# SCH_02_Electrodes.net
KiCad netlist of a schematic drawn in Altium Designer
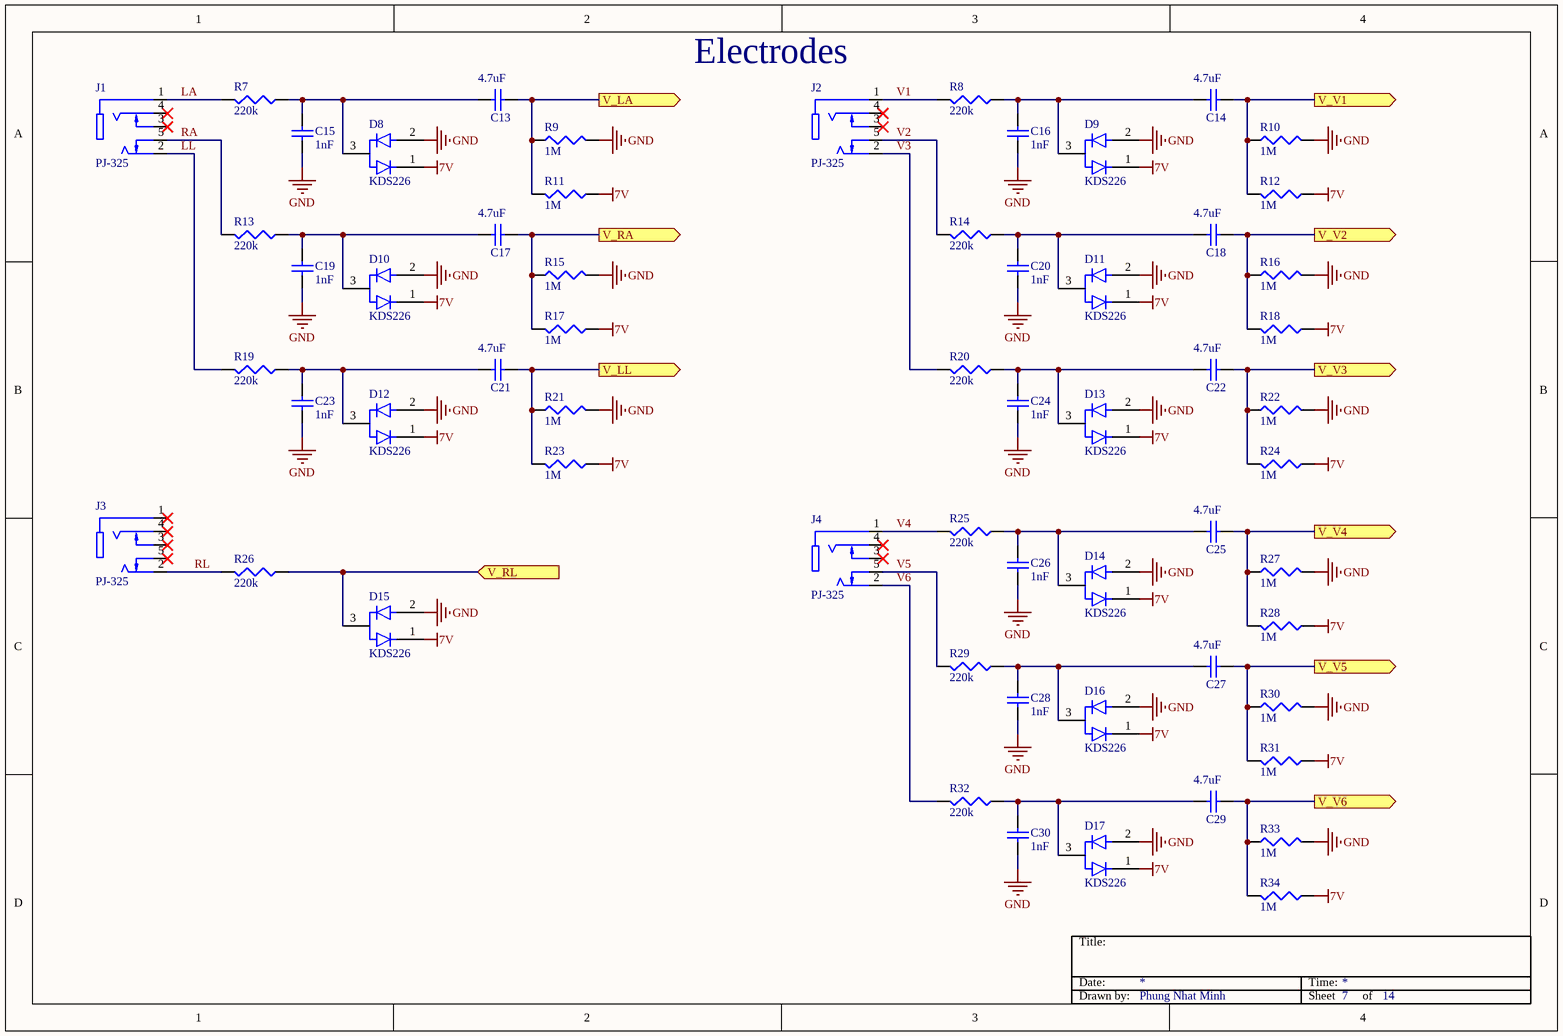
[diagram p0: SCH_02_Electrodes.SchDoc]

(export (version "E")
  (design (tool "Eeschema 10.0.6"))
  (components
    (comp (ref "C13")
      (value "4.7uF")
      (footprint "WCAP-CSGP_0603_L1.6W0.8H0.8_Reflow")
      (description "WCAP-CSGP Multilayer Ceramic Chip Capacitor, General Purpose, size 0603, X5R, 4.7uF, 10VDC")
      (fields
        (field (name "MANUFACTURER PART NUMBER") "885012106012")
        (field (name "MANUFACTURER") "Wurth Elektronik")
      )
      (libsource (lib "Altium_WCAP-CSGP (rev24b)") (part "885012106012"))
    )
    (comp (ref "C14")
      (value "4.7uF")
      (footprint "WCAP-CSGP_0603_L1.6W0.8H0.8_Reflow")
      (description "WCAP-CSGP Multilayer Ceramic Chip Capacitor, General Purpose, size 0603, X5R, 4.7uF, 10VDC")
      (fields
        (field (name "MANUFACTURER PART NUMBER") "885012106012")
        (field (name "MANUFACTURER") "Wurth Elektronik")
      )
      (libsource (lib "Altium_WCAP-CSGP (rev24b)") (part "885012106012"))
    )
    (comp (ref "C15")
      (value "1nF")
      (footprint "WCAP-CSGP_0603_L1.6W0.8H0.8_Reflow")
      (description "WCAP-CSGP Multilayer Ceramic Chip Capacitor, General Purpose, size 0603, NP0, 1nF, 50VDC")
      (fields
        (field (name "MANUFACTURER PART NUMBER") "885012006063")
        (field (name "MANUFACTURER") "Wurth Elektronik")
      )
      (libsource (lib "Altium_WCAP-CSGP (rev24b)") (part "885012006063"))
    )
    (comp (ref "C16")
      (value "1nF")
      (footprint "WCAP-CSGP_0603_L1.6W0.8H0.8_Reflow")
      (description "WCAP-CSGP Multilayer Ceramic Chip Capacitor, General Purpose, size 0603, NP0, 1nF, 50VDC")
      (fields
        (field (name "MANUFACTURER PART NUMBER") "885012006063")
        (field (name "MANUFACTURER") "Wurth Elektronik")
      )
      (libsource (lib "Altium_WCAP-CSGP (rev24b)") (part "885012006063"))
    )
    (comp (ref "C17")
      (value "4.7uF")
      (footprint "WCAP-CSGP_0603_L1.6W0.8H0.8_Reflow")
      (description "WCAP-CSGP Multilayer Ceramic Chip Capacitor, General Purpose, size 0603, X5R, 4.7uF, 10VDC")
      (fields
        (field (name "MANUFACTURER PART NUMBER") "885012106012")
        (field (name "MANUFACTURER") "Wurth Elektronik")
      )
      (libsource (lib "Altium_WCAP-CSGP (rev24b)") (part "885012106012"))
    )
    (comp (ref "C18")
      (value "4.7uF")
      (footprint "WCAP-CSGP_0603_L1.6W0.8H0.8_Reflow")
      (description "WCAP-CSGP Multilayer Ceramic Chip Capacitor, General Purpose, size 0603, X5R, 4.7uF, 10VDC")
      (fields
        (field (name "MANUFACTURER PART NUMBER") "885012106012")
        (field (name "MANUFACTURER") "Wurth Elektronik")
      )
      (libsource (lib "Altium_WCAP-CSGP (rev24b)") (part "885012106012"))
    )
    (comp (ref "C19")
      (value "1nF")
      (footprint "WCAP-CSGP_0603_L1.6W0.8H0.8_Reflow")
      (description "WCAP-CSGP Multilayer Ceramic Chip Capacitor, General Purpose, size 0603, NP0, 1nF, 50VDC")
      (fields
        (field (name "MANUFACTURER PART NUMBER") "885012006063")
        (field (name "MANUFACTURER") "Wurth Elektronik")
      )
      (libsource (lib "Altium_WCAP-CSGP (rev24b)") (part "885012006063"))
    )
    (comp (ref "C20")
      (value "1nF")
      (footprint "WCAP-CSGP_0603_L1.6W0.8H0.8_Reflow")
      (description "WCAP-CSGP Multilayer Ceramic Chip Capacitor, General Purpose, size 0603, NP0, 1nF, 50VDC")
      (fields
        (field (name "MANUFACTURER PART NUMBER") "885012006063")
        (field (name "MANUFACTURER") "Wurth Elektronik")
      )
      (libsource (lib "Altium_WCAP-CSGP (rev24b)") (part "885012006063"))
    )
    (comp (ref "C21")
      (value "4.7uF")
      (footprint "WCAP-CSGP_0603_L1.6W0.8H0.8_Reflow")
      (description "WCAP-CSGP Multilayer Ceramic Chip Capacitor, General Purpose, size 0603, X5R, 4.7uF, 10VDC")
      (fields
        (field (name "MANUFACTURER PART NUMBER") "885012106012")
        (field (name "MANUFACTURER") "Wurth Elektronik")
      )
      (libsource (lib "Altium_WCAP-CSGP (rev24b)") (part "885012106012"))
    )
    (comp (ref "C22")
      (value "4.7uF")
      (footprint "WCAP-CSGP_0603_L1.6W0.8H0.8_Reflow")
      (description "WCAP-CSGP Multilayer Ceramic Chip Capacitor, General Purpose, size 0603, X5R, 4.7uF, 10VDC")
      (fields
        (field (name "MANUFACTURER PART NUMBER") "885012106012")
        (field (name "MANUFACTURER") "Wurth Elektronik")
      )
      (libsource (lib "Altium_WCAP-CSGP (rev24b)") (part "885012106012"))
    )
    (comp (ref "C23")
      (value "1nF")
      (footprint "WCAP-CSGP_0603_L1.6W0.8H0.8_Reflow")
      (description "WCAP-CSGP Multilayer Ceramic Chip Capacitor, General Purpose, size 0603, NP0, 1nF, 50VDC")
      (fields
        (field (name "MANUFACTURER PART NUMBER") "885012006063")
        (field (name "MANUFACTURER") "Wurth Elektronik")
      )
      (libsource (lib "Altium_WCAP-CSGP (rev24b)") (part "885012006063"))
    )
    (comp (ref "C24")
      (value "1nF")
      (footprint "WCAP-CSGP_0603_L1.6W0.8H0.8_Reflow")
      (description "WCAP-CSGP Multilayer Ceramic Chip Capacitor, General Purpose, size 0603, NP0, 1nF, 50VDC")
      (fields
        (field (name "MANUFACTURER PART NUMBER") "885012006063")
        (field (name "MANUFACTURER") "Wurth Elektronik")
      )
      (libsource (lib "Altium_WCAP-CSGP (rev24b)") (part "885012006063"))
    )
    (comp (ref "C25")
      (value "4.7uF")
      (footprint "WCAP-CSGP_0603_L1.6W0.8H0.8_Reflow")
      (description "WCAP-CSGP Multilayer Ceramic Chip Capacitor, General Purpose, size 0603, X5R, 4.7uF, 10VDC")
      (fields
        (field (name "MANUFACTURER PART NUMBER") "885012106012")
        (field (name "MANUFACTURER") "Wurth Elektronik")
      )
      (libsource (lib "Altium_WCAP-CSGP (rev24b)") (part "885012106012"))
    )
    (comp (ref "C26")
      (value "1nF")
      (footprint "WCAP-CSGP_0603_L1.6W0.8H0.8_Reflow")
      (description "WCAP-CSGP Multilayer Ceramic Chip Capacitor, General Purpose, size 0603, NP0, 1nF, 50VDC")
      (fields
        (field (name "MANUFACTURER PART NUMBER") "885012006063")
        (field (name "MANUFACTURER") "Wurth Elektronik")
      )
      (libsource (lib "Altium_WCAP-CSGP (rev24b)") (part "885012006063"))
    )
    (comp (ref "C27")
      (value "4.7uF")
      (footprint "WCAP-CSGP_0603_L1.6W0.8H0.8_Reflow")
      (description "WCAP-CSGP Multilayer Ceramic Chip Capacitor, General Purpose, size 0603, X5R, 4.7uF, 10VDC")
      (fields
        (field (name "MANUFACTURER PART NUMBER") "885012106012")
        (field (name "MANUFACTURER") "Wurth Elektronik")
      )
      (libsource (lib "Altium_WCAP-CSGP (rev24b)") (part "885012106012"))
    )
    (comp (ref "C28")
      (value "1nF")
      (footprint "WCAP-CSGP_0603_L1.6W0.8H0.8_Reflow")
      (description "WCAP-CSGP Multilayer Ceramic Chip Capacitor, General Purpose, size 0603, NP0, 1nF, 50VDC")
      (fields
        (field (name "MANUFACTURER PART NUMBER") "885012006063")
        (field (name "MANUFACTURER") "Wurth Elektronik")
      )
      (libsource (lib "Altium_WCAP-CSGP (rev24b)") (part "885012006063"))
    )
    (comp (ref "C29")
      (value "4.7uF")
      (footprint "WCAP-CSGP_0603_L1.6W0.8H0.8_Reflow")
      (description "WCAP-CSGP Multilayer Ceramic Chip Capacitor, General Purpose, size 0603, X5R, 4.7uF, 10VDC")
      (fields
        (field (name "MANUFACTURER PART NUMBER") "885012106012")
        (field (name "MANUFACTURER") "Wurth Elektronik")
      )
      (libsource (lib "Altium_WCAP-CSGP (rev24b)") (part "885012106012"))
    )
    (comp (ref "C30")
      (value "1nF")
      (footprint "WCAP-CSGP_0603_L1.6W0.8H0.8_Reflow")
      (description "WCAP-CSGP Multilayer Ceramic Chip Capacitor, General Purpose, size 0603, NP0, 1nF, 50VDC")
      (fields
        (field (name "MANUFACTURER PART NUMBER") "885012006063")
        (field (name "MANUFACTURER") "Wurth Elektronik")
      )
      (libsource (lib "Altium_WCAP-CSGP (rev24b)") (part "885012006063"))
    )
    (comp (ref "D8")
      (value "KDS226")
      (footprint "DIO_BAV99")
      (fields (field (name "MP") "BAV99") (field (name "MF") "ON Semiconductor"))
      (libsource (lib "KDS226") (part "KDS226"))
    )
    (comp (ref "D9")
      (value "KDS226")
      (footprint "DIO_BAV99")
      (fields (field (name "MP") "BAV99") (field (name "MF") "ON Semiconductor"))
      (libsource (lib "KDS226") (part "KDS226"))
    )
    (comp (ref "D10")
      (value "KDS226")
      (footprint "DIO_BAV99")
      (fields (field (name "MP") "BAV99") (field (name "MF") "ON Semiconductor"))
      (libsource (lib "KDS226") (part "KDS226"))
    )
    (comp (ref "D11")
      (value "KDS226")
      (footprint "DIO_BAV99")
      (fields (field (name "MP") "BAV99") (field (name "MF") "ON Semiconductor"))
      (libsource (lib "KDS226") (part "KDS226"))
    )
    (comp (ref "D12")
      (value "KDS226")
      (footprint "DIO_BAV99")
      (fields (field (name "MP") "BAV99") (field (name "MF") "ON Semiconductor"))
      (libsource (lib "KDS226") (part "KDS226"))
    )
    (comp (ref "D13")
      (value "KDS226")
      (footprint "DIO_BAV99")
      (fields (field (name "MP") "BAV99") (field (name "MF") "ON Semiconductor"))
      (libsource (lib "KDS226") (part "KDS226"))
    )
    (comp (ref "D14")
      (value "KDS226")
      (footprint "DIO_BAV99")
      (fields (field (name "MP") "BAV99") (field (name "MF") "ON Semiconductor"))
      (libsource (lib "KDS226") (part "KDS226"))
    )
    (comp (ref "D15")
      (value "KDS226")
      (footprint "DIO_BAV99")
      (fields (field (name "MP") "BAV99") (field (name "MF") "ON Semiconductor"))
      (libsource (lib "KDS226") (part "KDS226"))
    )
    (comp (ref "D16")
      (value "KDS226")
      (footprint "DIO_BAV99")
      (fields (field (name "MP") "BAV99") (field (name "MF") "ON Semiconductor"))
      (libsource (lib "KDS226") (part "KDS226"))
    )
    (comp (ref "D17")
      (value "KDS226")
      (footprint "DIO_BAV99")
      (fields (field (name "MP") "BAV99") (field (name "MF") "ON Semiconductor"))
      (libsource (lib "KDS226") (part "KDS226"))
    )
    (comp (ref "J1")
      (value "PJ-325")
      (footprint "3.5 mm, Strereo")
      (description "Jack 3.5 3-Pole 5-Pin")
      (fields (field (name "Comment") "PJ-324"))
      (libsource (lib "Giang's Libs") (part "PJ-324"))
    )
    (comp (ref "J2")
      (value "PJ-325")
      (footprint "3.5 mm, Strereo")
      (description "Jack 3.5 3-Pole 5-Pin")
      (fields (field (name "Comment") "PJ-324"))
      (libsource (lib "Giang's Libs") (part "PJ-324"))
    )
    (comp (ref "J3")
      (value "PJ-325")
      (footprint "3.5 mm, Strereo")
      (description "Jack 3.5 3-Pole 5-Pin")
      (fields (field (name "Comment") "PJ-324"))
      (libsource (lib "Giang's Libs") (part "PJ-324"))
    )
    (comp (ref "J4")
      (value "PJ-325")
      (footprint "3.5 mm, Strereo")
      (description "Jack 3.5 3-Pole 5-Pin")
      (fields (field (name "Comment") "PJ-324"))
      (libsource (lib "Giang's Libs") (part "PJ-324"))
    )
    (comp (ref "R7")
      (value "220k")
      (footprint "WRIS-PSMB_0603_L1.6W0.8H0.35")
      (description "WRIS-PSMB Metal Plate Resistor, SMT, size 0603, 0.33W, 5mΩ, +/-1%")
      (fields
        (field (name "MANUFACTURER PART NUMBER") "580060716001")
        (field (name "MANUFACTURER") "Wurth Elektronik")
      )
      (libsource (lib "Altium_WRIS-PSMB (rev22a)") (part "580060716001"))
    )
    (comp (ref "R8")
      (value "220k")
      (footprint "WRIS-PSMB_0603_L1.6W0.8H0.35")
      (description "WRIS-PSMB Metal Plate Resistor, SMT, size 0603, 0.33W, 5mΩ, +/-1%")
      (fields
        (field (name "MANUFACTURER PART NUMBER") "580060716001")
        (field (name "MANUFACTURER") "Wurth Elektronik")
      )
      (libsource (lib "Altium_WRIS-PSMB (rev22a)") (part "580060716001"))
    )
    (comp (ref "R9")
      (value "1M")
      (footprint "WRIS-PSMB_0603_L1.6W0.8H0.35")
      (description "WRIS-PSMB Metal Plate Resistor, SMT, size 0603, 0.33W, 5mΩ, +/-1%")
      (fields
        (field (name "MANUFACTURER PART NUMBER") "580060716001")
        (field (name "MANUFACTURER") "Wurth Elektronik")
      )
      (libsource (lib "Altium_WRIS-PSMB (rev22a)") (part "580060716001"))
    )
    (comp (ref "R10")
      (value "1M")
      (footprint "WRIS-PSMB_0603_L1.6W0.8H0.35")
      (description "WRIS-PSMB Metal Plate Resistor, SMT, size 0603, 0.33W, 5mΩ, +/-1%")
      (fields
        (field (name "MANUFACTURER PART NUMBER") "580060716001")
        (field (name "MANUFACTURER") "Wurth Elektronik")
      )
      (libsource (lib "Altium_WRIS-PSMB (rev22a)") (part "580060716001"))
    )
    (comp (ref "R11")
      (value "1M")
      (footprint "WRIS-PSMB_0603_L1.6W0.8H0.35")
      (description "WRIS-PSMB Metal Plate Resistor, SMT, size 0603, 0.33W, 5mΩ, +/-1%")
      (fields
        (field (name "MANUFACTURER PART NUMBER") "580060716001")
        (field (name "MANUFACTURER") "Wurth Elektronik")
      )
      (libsource (lib "Altium_WRIS-PSMB (rev22a)") (part "580060716001"))
    )
    (comp (ref "R12")
      (value "1M")
      (footprint "WRIS-PSMB_0603_L1.6W0.8H0.35")
      (description "WRIS-PSMB Metal Plate Resistor, SMT, size 0603, 0.33W, 5mΩ, +/-1%")
      (fields
        (field (name "MANUFACTURER PART NUMBER") "580060716001")
        (field (name "MANUFACTURER") "Wurth Elektronik")
      )
      (libsource (lib "Altium_WRIS-PSMB (rev22a)") (part "580060716001"))
    )
    (comp (ref "R13")
      (value "220k")
      (footprint "WRIS-PSMB_0603_L1.6W0.8H0.35")
      (description "WRIS-PSMB Metal Plate Resistor, SMT, size 0603, 0.33W, 5mΩ, +/-1%")
      (fields
        (field (name "MANUFACTURER PART NUMBER") "580060716001")
        (field (name "MANUFACTURER") "Wurth Elektronik")
      )
      (libsource (lib "Altium_WRIS-PSMB (rev22a)") (part "580060716001"))
    )
    (comp (ref "R14")
      (value "220k")
      (footprint "WRIS-PSMB_0603_L1.6W0.8H0.35")
      (description "WRIS-PSMB Metal Plate Resistor, SMT, size 0603, 0.33W, 5mΩ, +/-1%")
      (fields
        (field (name "MANUFACTURER PART NUMBER") "580060716001")
        (field (name "MANUFACTURER") "Wurth Elektronik")
      )
      (libsource (lib "Altium_WRIS-PSMB (rev22a)") (part "580060716001"))
    )
    (comp (ref "R15")
      (value "1M")
      (footprint "WRIS-PSMB_0603_L1.6W0.8H0.35")
      (description "WRIS-PSMB Metal Plate Resistor, SMT, size 0603, 0.33W, 5mΩ, +/-1%")
      (fields
        (field (name "MANUFACTURER PART NUMBER") "580060716001")
        (field (name "MANUFACTURER") "Wurth Elektronik")
      )
      (libsource (lib "Altium_WRIS-PSMB (rev22a)") (part "580060716001"))
    )
    (comp (ref "R16")
      (value "1M")
      (footprint "WRIS-PSMB_0603_L1.6W0.8H0.35")
      (description "WRIS-PSMB Metal Plate Resistor, SMT, size 0603, 0.33W, 5mΩ, +/-1%")
      (fields
        (field (name "MANUFACTURER PART NUMBER") "580060716001")
        (field (name "MANUFACTURER") "Wurth Elektronik")
      )
      (libsource (lib "Altium_WRIS-PSMB (rev22a)") (part "580060716001"))
    )
    (comp (ref "R17")
      (value "1M")
      (footprint "WRIS-PSMB_0603_L1.6W0.8H0.35")
      (description "WRIS-PSMB Metal Plate Resistor, SMT, size 0603, 0.33W, 5mΩ, +/-1%")
      (fields
        (field (name "MANUFACTURER PART NUMBER") "580060716001")
        (field (name "MANUFACTURER") "Wurth Elektronik")
      )
      (libsource (lib "Altium_WRIS-PSMB (rev22a)") (part "580060716001"))
    )
    (comp (ref "R18")
      (value "1M")
      (footprint "WRIS-PSMB_0603_L1.6W0.8H0.35")
      (description "WRIS-PSMB Metal Plate Resistor, SMT, size 0603, 0.33W, 5mΩ, +/-1%")
      (fields
        (field (name "MANUFACTURER PART NUMBER") "580060716001")
        (field (name "MANUFACTURER") "Wurth Elektronik")
      )
      (libsource (lib "Altium_WRIS-PSMB (rev22a)") (part "580060716001"))
    )
    (comp (ref "R19")
      (value "220k")
      (footprint "WRIS-PSMB_0603_L1.6W0.8H0.35")
      (description "WRIS-PSMB Metal Plate Resistor, SMT, size 0603, 0.33W, 5mΩ, +/-1%")
      (fields
        (field (name "MANUFACTURER PART NUMBER") "580060716001")
        (field (name "MANUFACTURER") "Wurth Elektronik")
      )
      (libsource (lib "Altium_WRIS-PSMB (rev22a)") (part "580060716001"))
    )
    (comp (ref "R20")
      (value "220k")
      (footprint "WRIS-PSMB_0603_L1.6W0.8H0.35")
      (description "WRIS-PSMB Metal Plate Resistor, SMT, size 0603, 0.33W, 5mΩ, +/-1%")
      (fields
        (field (name "MANUFACTURER PART NUMBER") "580060716001")
        (field (name "MANUFACTURER") "Wurth Elektronik")
      )
      (libsource (lib "Altium_WRIS-PSMB (rev22a)") (part "580060716001"))
    )
    (comp (ref "R21")
      (value "1M")
      (footprint "WRIS-PSMB_0603_L1.6W0.8H0.35")
      (description "WRIS-PSMB Metal Plate Resistor, SMT, size 0603, 0.33W, 5mΩ, +/-1%")
      (fields
        (field (name "MANUFACTURER PART NUMBER") "580060716001")
        (field (name "MANUFACTURER") "Wurth Elektronik")
      )
      (libsource (lib "Altium_WRIS-PSMB (rev22a)") (part "580060716001"))
    )
    (comp (ref "R22")
      (value "1M")
      (footprint "WRIS-PSMB_0603_L1.6W0.8H0.35")
      (description "WRIS-PSMB Metal Plate Resistor, SMT, size 0603, 0.33W, 5mΩ, +/-1%")
      (fields
        (field (name "MANUFACTURER PART NUMBER") "580060716001")
        (field (name "MANUFACTURER") "Wurth Elektronik")
      )
      (libsource (lib "Altium_WRIS-PSMB (rev22a)") (part "580060716001"))
    )
    (comp (ref "R23")
      (value "1M")
      (footprint "WRIS-PSMB_0603_L1.6W0.8H0.35")
      (description "WRIS-PSMB Metal Plate Resistor, SMT, size 0603, 0.33W, 5mΩ, +/-1%")
      (fields
        (field (name "MANUFACTURER PART NUMBER") "580060716001")
        (field (name "MANUFACTURER") "Wurth Elektronik")
      )
      (libsource (lib "Altium_WRIS-PSMB (rev22a)") (part "580060716001"))
    )
    (comp (ref "R24")
      (value "1M")
      (footprint "WRIS-PSMB_0603_L1.6W0.8H0.35")
      (description "WRIS-PSMB Metal Plate Resistor, SMT, size 0603, 0.33W, 5mΩ, +/-1%")
      (fields
        (field (name "MANUFACTURER PART NUMBER") "580060716001")
        (field (name "MANUFACTURER") "Wurth Elektronik")
      )
      (libsource (lib "Altium_WRIS-PSMB (rev22a)") (part "580060716001"))
    )
    (comp (ref "R25")
      (value "220k")
      (footprint "WRIS-PSMB_0603_L1.6W0.8H0.35")
      (description "WRIS-PSMB Metal Plate Resistor, SMT, size 0603, 0.33W, 5mΩ, +/-1%")
      (fields
        (field (name "MANUFACTURER PART NUMBER") "580060716001")
        (field (name "MANUFACTURER") "Wurth Elektronik")
      )
      (libsource (lib "Altium_WRIS-PSMB (rev22a)") (part "580060716001"))
    )
    (comp (ref "R26")
      (value "220k")
      (footprint "WRIS-PSMB_0603_L1.6W0.8H0.35")
      (description "WRIS-PSMB Metal Plate Resistor, SMT, size 0603, 0.33W, 5mΩ, +/-1%")
      (fields
        (field (name "MANUFACTURER PART NUMBER") "580060716001")
        (field (name "MANUFACTURER") "Wurth Elektronik")
      )
      (libsource (lib "Altium_WRIS-PSMB (rev22a)") (part "580060716001"))
    )
    (comp (ref "R27")
      (value "1M")
      (footprint "WRIS-PSMB_0603_L1.6W0.8H0.35")
      (description "WRIS-PSMB Metal Plate Resistor, SMT, size 0603, 0.33W, 5mΩ, +/-1%")
      (fields
        (field (name "MANUFACTURER PART NUMBER") "580060716001")
        (field (name "MANUFACTURER") "Wurth Elektronik")
      )
      (libsource (lib "Altium_WRIS-PSMB (rev22a)") (part "580060716001"))
    )
    (comp (ref "R28")
      (value "1M")
      (footprint "WRIS-PSMB_0603_L1.6W0.8H0.35")
      (description "WRIS-PSMB Metal Plate Resistor, SMT, size 0603, 0.33W, 5mΩ, +/-1%")
      (fields
        (field (name "MANUFACTURER PART NUMBER") "580060716001")
        (field (name "MANUFACTURER") "Wurth Elektronik")
      )
      (libsource (lib "Altium_WRIS-PSMB (rev22a)") (part "580060716001"))
    )
    (comp (ref "R29")
      (value "220k")
      (footprint "WRIS-PSMB_0603_L1.6W0.8H0.35")
      (description "WRIS-PSMB Metal Plate Resistor, SMT, size 0603, 0.33W, 5mΩ, +/-1%")
      (fields
        (field (name "MANUFACTURER PART NUMBER") "580060716001")
        (field (name "MANUFACTURER") "Wurth Elektronik")
      )
      (libsource (lib "Altium_WRIS-PSMB (rev22a)") (part "580060716001"))
    )
    (comp (ref "R30")
      (value "1M")
      (footprint "WRIS-PSMB_0603_L1.6W0.8H0.35")
      (description "WRIS-PSMB Metal Plate Resistor, SMT, size 0603, 0.33W, 5mΩ, +/-1%")
      (fields
        (field (name "MANUFACTURER PART NUMBER") "580060716001")
        (field (name "MANUFACTURER") "Wurth Elektronik")
      )
      (libsource (lib "Altium_WRIS-PSMB (rev22a)") (part "580060716001"))
    )
    (comp (ref "R31")
      (value "1M")
      (footprint "WRIS-PSMB_0603_L1.6W0.8H0.35")
      (description "WRIS-PSMB Metal Plate Resistor, SMT, size 0603, 0.33W, 5mΩ, +/-1%")
      (fields
        (field (name "MANUFACTURER PART NUMBER") "580060716001")
        (field (name "MANUFACTURER") "Wurth Elektronik")
      )
      (libsource (lib "Altium_WRIS-PSMB (rev22a)") (part "580060716001"))
    )
    (comp (ref "R32")
      (value "220k")
      (footprint "WRIS-PSMB_0603_L1.6W0.8H0.35")
      (description "WRIS-PSMB Metal Plate Resistor, SMT, size 0603, 0.33W, 5mΩ, +/-1%")
      (fields
        (field (name "MANUFACTURER PART NUMBER") "580060716001")
        (field (name "MANUFACTURER") "Wurth Elektronik")
      )
      (libsource (lib "Altium_WRIS-PSMB (rev22a)") (part "580060716001"))
    )
    (comp (ref "R33")
      (value "1M")
      (footprint "WRIS-PSMB_0603_L1.6W0.8H0.35")
      (description "WRIS-PSMB Metal Plate Resistor, SMT, size 0603, 0.33W, 5mΩ, +/-1%")
      (fields
        (field (name "MANUFACTURER PART NUMBER") "580060716001")
        (field (name "MANUFACTURER") "Wurth Elektronik")
      )
      (libsource (lib "Altium_WRIS-PSMB (rev22a)") (part "580060716001"))
    )
    (comp (ref "R34")
      (value "1M")
      (footprint "WRIS-PSMB_0603_L1.6W0.8H0.35")
      (description "WRIS-PSMB Metal Plate Resistor, SMT, size 0603, 0.33W, 5mΩ, +/-1%")
      (fields
        (field (name "MANUFACTURER PART NUMBER") "580060716001")
        (field (name "MANUFACTURER") "Wurth Elektronik")
      )
      (libsource (lib "Altium_WRIS-PSMB (rev22a)") (part "580060716001"))
    )
  )
  (nets
    (net (code "1") (name "/LA") (class "Default")
      (node (ref "J1") (pin "1") (pinfunction "1_1") (pintype "passive"))
      (node (ref "R7") (pin "2") (pinfunction "2_2") (pintype "passive"))
    )
    (net (code "2") (name "/LL") (class "Default")
      (node (ref "J1") (pin "2") (pinfunction "2_2") (pintype "passive"))
      (node (ref "R19") (pin "2") (pinfunction "2_2") (pintype "passive"))
    )
    (net (code "3") (name "/RA") (class "Default")
      (node (ref "J1") (pin "5") (pinfunction "5_5") (pintype "passive"))
      (node (ref "R13") (pin "2") (pinfunction "2_2") (pintype "passive"))
    )
    (net (code "4") (name "/RL") (class "Default")
      (node (ref "J3") (pin "2") (pinfunction "2_2") (pintype "passive"))
      (node (ref "R26") (pin "2") (pinfunction "2_2") (pintype "passive"))
    )
    (net (code "5") (name "/V1") (class "Default")
      (node (ref "J2") (pin "1") (pinfunction "1_1") (pintype "passive"))
      (node (ref "R8") (pin "2") (pinfunction "2_2") (pintype "passive"))
    )
    (net (code "6") (name "/V2") (class "Default")
      (node (ref "J2") (pin "5") (pinfunction "5_5") (pintype "passive"))
      (node (ref "R14") (pin "2") (pinfunction "2_2") (pintype "passive"))
    )
    (net (code "7") (name "/V3") (class "Default")
      (node (ref "J2") (pin "2") (pinfunction "2_2") (pintype "passive"))
      (node (ref "R20") (pin "2") (pinfunction "2_2") (pintype "passive"))
    )
    (net (code "8") (name "/V4") (class "Default")
      (node (ref "J4") (pin "1") (pinfunction "1_1") (pintype "passive"))
      (node (ref "R25") (pin "2") (pinfunction "2_2") (pintype "passive"))
    )
    (net (code "9") (name "/V5") (class "Default")
      (node (ref "J4") (pin "5") (pinfunction "5_5") (pintype "passive"))
      (node (ref "R29") (pin "2") (pinfunction "2_2") (pintype "passive"))
    )
    (net (code "10") (name "/V6") (class "Default")
      (node (ref "J4") (pin "2") (pinfunction "2_2") (pintype "passive"))
      (node (ref "R32") (pin "2") (pinfunction "2_2") (pintype "passive"))
    )
    (net (code "11") (name "/V_LA") (class "Default")
      (node (ref "C13") (pin "2") (pinfunction "2_2") (pintype "passive"))
      (node (ref "R11") (pin "2") (pinfunction "2_2") (pintype "passive"))
      (node (ref "R9") (pin "1") (pinfunction "1_1") (pintype "passive"))
    )
    (net (code "12") (name "/V_LL") (class "Default")
      (node (ref "C21") (pin "2") (pinfunction "2_2") (pintype "passive"))
      (node (ref "R21") (pin "1") (pinfunction "1_1") (pintype "passive"))
      (node (ref "R23") (pin "2") (pinfunction "2_2") (pintype "passive"))
    )
    (net (code "13") (name "/V_RA") (class "Default")
      (node (ref "C17") (pin "2") (pinfunction "2_2") (pintype "passive"))
      (node (ref "R15") (pin "1") (pinfunction "1_1") (pintype "passive"))
      (node (ref "R17") (pin "2") (pinfunction "2_2") (pintype "passive"))
    )
    (net (code "14") (name "/V_RL") (class "Default")
      (node (ref "D15") (pin "3") (pinfunction "3_3") (pintype "passive"))
      (node (ref "R26") (pin "1") (pinfunction "1_1") (pintype "passive"))
    )
    (net (code "15") (name "/V_V1") (class "Default")
      (node (ref "C14") (pin "2") (pinfunction "2_2") (pintype "passive"))
      (node (ref "R10") (pin "1") (pinfunction "1_1") (pintype "passive"))
      (node (ref "R12") (pin "2") (pinfunction "2_2") (pintype "passive"))
    )
    (net (code "16") (name "/V_V2") (class "Default")
      (node (ref "C18") (pin "2") (pinfunction "2_2") (pintype "passive"))
      (node (ref "R16") (pin "1") (pinfunction "1_1") (pintype "passive"))
      (node (ref "R18") (pin "2") (pinfunction "2_2") (pintype "passive"))
    )
    (net (code "17") (name "/V_V3") (class "Default")
      (node (ref "C22") (pin "2") (pinfunction "2_2") (pintype "passive"))
      (node (ref "R22") (pin "1") (pinfunction "1_1") (pintype "passive"))
      (node (ref "R24") (pin "2") (pinfunction "2_2") (pintype "passive"))
    )
    (net (code "18") (name "/V_V4") (class "Default")
      (node (ref "C25") (pin "2") (pinfunction "2_2") (pintype "passive"))
      (node (ref "R27") (pin "1") (pinfunction "1_1") (pintype "passive"))
      (node (ref "R28") (pin "2") (pinfunction "2_2") (pintype "passive"))
    )
    (net (code "19") (name "/V_V5") (class "Default")
      (node (ref "C27") (pin "2") (pinfunction "2_2") (pintype "passive"))
      (node (ref "R30") (pin "1") (pinfunction "1_1") (pintype "passive"))
      (node (ref "R31") (pin "2") (pinfunction "2_2") (pintype "passive"))
    )
    (net (code "20") (name "/V_V6") (class "Default")
      (node (ref "C29") (pin "2") (pinfunction "2_2") (pintype "passive"))
      (node (ref "R33") (pin "1") (pinfunction "1_1") (pintype "passive"))
      (node (ref "R34") (pin "2") (pinfunction "2_2") (pintype "passive"))
    )
    (net (code "21") (name "7V") (class "Default")
      (node (ref "D10") (pin "1") (pinfunction "1_1") (pintype "passive"))
      (node (ref "D11") (pin "1") (pinfunction "1_1") (pintype "passive"))
      (node (ref "D12") (pin "1") (pinfunction "1_1") (pintype "passive"))
      (node (ref "D13") (pin "1") (pinfunction "1_1") (pintype "passive"))
      (node (ref "D14") (pin "1") (pinfunction "1_1") (pintype "passive"))
      (node (ref "D15") (pin "1") (pinfunction "1_1") (pintype "passive"))
      (node (ref "D16") (pin "1") (pinfunction "1_1") (pintype "passive"))
      (node (ref "D17") (pin "1") (pinfunction "1_1") (pintype "passive"))
      (node (ref "D8") (pin "1") (pinfunction "1_1") (pintype "passive"))
      (node (ref "D9") (pin "1") (pinfunction "1_1") (pintype "passive"))
      (node (ref "R11") (pin "1") (pinfunction "1_1") (pintype "passive"))
      (node (ref "R12") (pin "1") (pinfunction "1_1") (pintype "passive"))
      (node (ref "R17") (pin "1") (pinfunction "1_1") (pintype "passive"))
      (node (ref "R18") (pin "1") (pinfunction "1_1") (pintype "passive"))
      (node (ref "R23") (pin "1") (pinfunction "1_1") (pintype "passive"))
      (node (ref "R24") (pin "1") (pinfunction "1_1") (pintype "passive"))
      (node (ref "R28") (pin "1") (pinfunction "1_1") (pintype "passive"))
      (node (ref "R31") (pin "1") (pinfunction "1_1") (pintype "passive"))
      (node (ref "R34") (pin "1") (pinfunction "1_1") (pintype "passive"))
    )
    (net (code "22") (name "GND") (class "Default")
      (node (ref "C15") (pin "2") (pinfunction "2_2") (pintype "passive"))
      (node (ref "C16") (pin "2") (pinfunction "2_2") (pintype "passive"))
      (node (ref "C19") (pin "2") (pinfunction "2_2") (pintype "passive"))
      (node (ref "C20") (pin "2") (pinfunction "2_2") (pintype "passive"))
      (node (ref "C23") (pin "2") (pinfunction "2_2") (pintype "passive"))
      (node (ref "C24") (pin "2") (pinfunction "2_2") (pintype "passive"))
      (node (ref "C26") (pin "2") (pinfunction "2_2") (pintype "passive"))
      (node (ref "C28") (pin "2") (pinfunction "2_2") (pintype "passive"))
      (node (ref "C30") (pin "2") (pinfunction "2_2") (pintype "passive"))
      (node (ref "D10") (pin "2") (pinfunction "2_2") (pintype "passive"))
      (node (ref "D11") (pin "2") (pinfunction "2_2") (pintype "passive"))
      (node (ref "D12") (pin "2") (pinfunction "2_2") (pintype "passive"))
      (node (ref "D13") (pin "2") (pinfunction "2_2") (pintype "passive"))
      (node (ref "D14") (pin "2") (pinfunction "2_2") (pintype "passive"))
      (node (ref "D15") (pin "2") (pinfunction "2_2") (pintype "passive"))
      (node (ref "D16") (pin "2") (pinfunction "2_2") (pintype "passive"))
      (node (ref "D17") (pin "2") (pinfunction "2_2") (pintype "passive"))
      (node (ref "D8") (pin "2") (pinfunction "2_2") (pintype "passive"))
      (node (ref "D9") (pin "2") (pinfunction "2_2") (pintype "passive"))
      (node (ref "R10") (pin "2") (pinfunction "2_2") (pintype "passive"))
      (node (ref "R15") (pin "2") (pinfunction "2_2") (pintype "passive"))
      (node (ref "R16") (pin "2") (pinfunction "2_2") (pintype "passive"))
      (node (ref "R21") (pin "2") (pinfunction "2_2") (pintype "passive"))
      (node (ref "R22") (pin "2") (pinfunction "2_2") (pintype "passive"))
      (node (ref "R27") (pin "2") (pinfunction "2_2") (pintype "passive"))
      (node (ref "R30") (pin "2") (pinfunction "2_2") (pintype "passive"))
      (node (ref "R33") (pin "2") (pinfunction "2_2") (pintype "passive"))
      (node (ref "R9") (pin "2") (pinfunction "2_2") (pintype "passive"))
    )
    (net (code "23") (name "Net-(C13-Pad1)") (class "Default")
      (node (ref "C13") (pin "1") (pinfunction "1_1") (pintype "passive"))
      (node (ref "C15") (pin "1") (pinfunction "1_1") (pintype "passive"))
      (node (ref "D8") (pin "3") (pinfunction "3_3") (pintype "passive"))
      (node (ref "R7") (pin "1") (pinfunction "1_1") (pintype "passive"))
    )
    (net (code "24") (name "Net-(C14-Pad1)") (class "Default")
      (node (ref "C14") (pin "1") (pinfunction "1_1") (pintype "passive"))
      (node (ref "C16") (pin "1") (pinfunction "1_1") (pintype "passive"))
      (node (ref "D9") (pin "3") (pinfunction "3_3") (pintype "passive"))
      (node (ref "R8") (pin "1") (pinfunction "1_1") (pintype "passive"))
    )
    (net (code "25") (name "Net-(C17-Pad1)") (class "Default")
      (node (ref "C17") (pin "1") (pinfunction "1_1") (pintype "passive"))
      (node (ref "C19") (pin "1") (pinfunction "1_1") (pintype "passive"))
      (node (ref "D10") (pin "3") (pinfunction "3_3") (pintype "passive"))
      (node (ref "R13") (pin "1") (pinfunction "1_1") (pintype "passive"))
    )
    (net (code "26") (name "Net-(C18-Pad1)") (class "Default")
      (node (ref "C18") (pin "1") (pinfunction "1_1") (pintype "passive"))
      (node (ref "C20") (pin "1") (pinfunction "1_1") (pintype "passive"))
      (node (ref "D11") (pin "3") (pinfunction "3_3") (pintype "passive"))
      (node (ref "R14") (pin "1") (pinfunction "1_1") (pintype "passive"))
    )
    (net (code "27") (name "Net-(C21-Pad1)") (class "Default")
      (node (ref "C21") (pin "1") (pinfunction "1_1") (pintype "passive"))
      (node (ref "C23") (pin "1") (pinfunction "1_1") (pintype "passive"))
      (node (ref "D12") (pin "3") (pinfunction "3_3") (pintype "passive"))
      (node (ref "R19") (pin "1") (pinfunction "1_1") (pintype "passive"))
    )
    (net (code "28") (name "Net-(C22-Pad1)") (class "Default")
      (node (ref "C22") (pin "1") (pinfunction "1_1") (pintype "passive"))
      (node (ref "C24") (pin "1") (pinfunction "1_1") (pintype "passive"))
      (node (ref "D13") (pin "3") (pinfunction "3_3") (pintype "passive"))
      (node (ref "R20") (pin "1") (pinfunction "1_1") (pintype "passive"))
    )
    (net (code "29") (name "Net-(C25-Pad1)") (class "Default")
      (node (ref "C25") (pin "1") (pinfunction "1_1") (pintype "passive"))
      (node (ref "C26") (pin "1") (pinfunction "1_1") (pintype "passive"))
      (node (ref "D14") (pin "3") (pinfunction "3_3") (pintype "passive"))
      (node (ref "R25") (pin "1") (pinfunction "1_1") (pintype "passive"))
    )
    (net (code "30") (name "Net-(C27-Pad1)") (class "Default")
      (node (ref "C27") (pin "1") (pinfunction "1_1") (pintype "passive"))
      (node (ref "C28") (pin "1") (pinfunction "1_1") (pintype "passive"))
      (node (ref "D16") (pin "3") (pinfunction "3_3") (pintype "passive"))
      (node (ref "R29") (pin "1") (pinfunction "1_1") (pintype "passive"))
    )
    (net (code "31") (name "Net-(C29-Pad1)") (class "Default")
      (node (ref "C29") (pin "1") (pinfunction "1_1") (pintype "passive"))
      (node (ref "C30") (pin "1") (pinfunction "1_1") (pintype "passive"))
      (node (ref "D17") (pin "3") (pinfunction "3_3") (pintype "passive"))
      (node (ref "R32") (pin "1") (pinfunction "1_1") (pintype "passive"))
    )
    (net (code "32") (name "unconnected-(J1-Pad3)") (class "Default")
      (node (ref "J1") (pin "3") (pinfunction "3_3") (pintype "passive+no_connect"))
    )
    (net (code "33") (name "unconnected-(J1-Pad4)") (class "Default")
      (node (ref "J1") (pin "4") (pinfunction "4_4") (pintype "passive+no_connect"))
    )
    (net (code "34") (name "unconnected-(J2-Pad3)") (class "Default")
      (node (ref "J2") (pin "3") (pinfunction "3_3") (pintype "passive+no_connect"))
    )
    (net (code "35") (name "unconnected-(J2-Pad4)") (class "Default")
      (node (ref "J2") (pin "4") (pinfunction "4_4") (pintype "passive+no_connect"))
    )
    (net (code "36") (name "unconnected-(J3-Pad1)") (class "Default")
      (node (ref "J3") (pin "1") (pinfunction "1_1") (pintype "passive+no_connect"))
    )
    (net (code "37") (name "unconnected-(J3-Pad3)") (class "Default")
      (node (ref "J3") (pin "3") (pinfunction "3_3") (pintype "passive+no_connect"))
    )
    (net (code "38") (name "unconnected-(J3-Pad4)") (class "Default")
      (node (ref "J3") (pin "4") (pinfunction "4_4") (pintype "passive+no_connect"))
    )
    (net (code "39") (name "unconnected-(J3-Pad5)") (class "Default")
      (node (ref "J3") (pin "5") (pinfunction "5_5") (pintype "passive+no_connect"))
    )
    (net (code "40") (name "unconnected-(J4-Pad3)") (class "Default")
      (node (ref "J4") (pin "3") (pinfunction "3_3") (pintype "passive+no_connect"))
    )
    (net (code "41") (name "unconnected-(J4-Pad4)") (class "Default")
      (node (ref "J4") (pin "4") (pinfunction "4_4") (pintype "passive+no_connect"))
    )
  )
)
